# SCH4_RGB_Indicator.net
KiCad netlist of a schematic drawn in Altium Designer
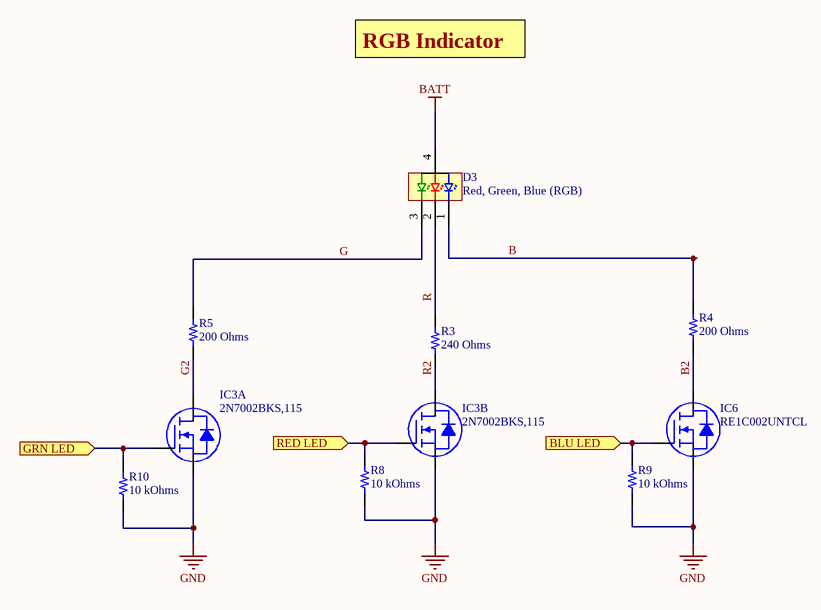
[diagram p0: SCH4_RGB_Indicator.SchDoc]

(export (version "E")
  (design (tool "Eeschema 10.0.6"))
  (components
    (comp (ref "D3")
      (value "Red, Green, Blue (RGB)")
      (footprint "Citizen CL-505S-X-SD-T")
      (description "LED TRI TOP FIRING 1.0 X 1.0")
      (fields (field (name "PART NUMBER") "CL-505S-X-SD-T") (field (name "MANUFACTURER") "Citizen"))
      (libsource (lib "Celestial Altium Library - altium_library") (part "RGB LED Citizen CL-505"))
    )
    (comp (ref "IC3")
      (value "2N7002BKS,115")
      (footprint "NXP SOT-363")
      (description "MOSFET 2N-CH 60V 0.3A 6TSSOP")
      (fields (field (name "MANUFACTURER") "Nexperia USA Inc."))
      (libsource (lib "Celestial Altium Library - altium_library") (part "NEXPERIA DUAL MOSFET N-CH SOT363"))
    )
    (comp (ref "IC6")
      (value "RE1C002UNTCL")
      (footprint "ROHM SC-89-SOT-490")
      (description "MOSFET N-CH 20V 0.2A EMT3")
      (fields (field (name "MANUFACTURER") "Rohm Semiconductor"))
      (libsource (lib "Celestial Altium Library - altium_library") (part "ROHM MOSFET N-CH SC-89"))
    )
    (comp (ref "R3")
      (value "240 Ohms")
      (footprint "RES 0402_1005")
      (description "RES SMD 240 OHM 0.5% 1/16W 0402")
      (fields (field (name "PART NUMBER") "RR0510P-241-D") (field (name "MANUFACTURER") "Susumu"))
      (libsource (lib "Celestial Altium Library - altium_library") (part "Resistor"))
    )
    (comp (ref "R4")
      (value "200 Ohms")
      (footprint "RES 0402_1005")
      (description "RES SMD 200 OHM 0.5% 1/16W 0402")
      (fields (field (name "PART NUMBER") "RR0510P-201-D") (field (name "MANUFACTURER") "Susumu"))
      (libsource (lib "Celestial Altium Library - altium_library") (part "Resistor"))
    )
    (comp (ref "R5")
      (value "200 Ohms")
      (footprint "RES 0402_1005")
      (description "RES SMD 200 OHM 0.5% 1/16W 0402")
      (fields (field (name "PART NUMBER") "RR0510P-201-D") (field (name "MANUFACTURER") "Susumu"))
      (libsource (lib "Celestial Altium Library - altium_library") (part "Resistor"))
    )
    (comp (ref "R8")
      (value "10 kOhms")
      (footprint "RES 0402_1005")
      (description "RES 10 KOHM 1% 1/16W 0402")
      (fields (field (name "PART NUMBER") "ASC0402-10KF1") (field (name "MANUFACTURER") "Riedon"))
      (libsource (lib "Celestial Altium Library - altium_library") (part "Resistor"))
    )
    (comp (ref "R9")
      (value "10 kOhms")
      (footprint "RES 0402_1005")
      (description "RES 10 KOHM 1% 1/16W 0402")
      (fields (field (name "PART NUMBER") "ASC0402-10KF1") (field (name "MANUFACTURER") "Riedon"))
      (libsource (lib "Celestial Altium Library - altium_library") (part "Resistor"))
    )
    (comp (ref "R10")
      (value "10 kOhms")
      (footprint "RES 0402_1005")
      (description "RES 10 KOHM 1% 1/16W 0402")
      (fields (field (name "PART NUMBER") "ASC0402-10KF1") (field (name "MANUFACTURER") "Riedon"))
      (libsource (lib "Celestial Altium Library - altium_library") (part "Resistor"))
    )
  )
  (nets
    (net (code "2") (name "/B") (class "Default")
      (node (ref "D3") (pin "1") (pinfunction "C1_1") (pintype "passive"))
      (node (ref "R4") (pin "2") (pinfunction "2_2") (pintype "passive"))
    )
    (net (code "3") (name "/B2") (class "Default")
      (node (ref "IC6") (pin "3") (pinfunction "D_3") (pintype "passive"))
      (node (ref "R4") (pin "1") (pinfunction "1_1") (pintype "passive"))
    )
    (net (code "4") (name "/BLU LED") (class "Default")
      (node (ref "IC6") (pin "1") (pinfunction "G_1") (pintype "passive"))
      (node (ref "R9") (pin "2") (pinfunction "2_2") (pintype "passive"))
    )
    (net (code "5") (name "/G") (class "Default")
      (node (ref "D3") (pin "3") (pinfunction "C3_3") (pintype "passive"))
      (node (ref "R5") (pin "2") (pinfunction "2_2") (pintype "passive"))
    )
    (net (code "6") (name "/G2") (class "Default")
      (node (ref "IC3") (pin "6") (pinfunction "D1_6") (pintype "passive"))
      (node (ref "R5") (pin "1") (pinfunction "1_1") (pintype "passive"))
    )
    (net (code "7") (name "/GRN LED") (class "Default")
      (node (ref "IC3") (pin "2") (pinfunction "G1_2") (pintype "passive"))
      (node (ref "R10") (pin "2") (pinfunction "2_2") (pintype "passive"))
    )
    (net (code "8") (name "/R") (class "Default")
      (node (ref "D3") (pin "2") (pinfunction "C2_2") (pintype "passive"))
      (node (ref "R3") (pin "2") (pinfunction "2_2") (pintype "passive"))
    )
    (net (code "9") (name "/R2") (class "Default")
      (node (ref "IC3") (pin "3") (pinfunction "D2_3") (pintype "passive"))
      (node (ref "R3") (pin "1") (pinfunction "1_1") (pintype "passive"))
    )
    (net (code "10") (name "/RED LED") (class "Default")
      (node (ref "IC3") (pin "5") (pinfunction "G2_5") (pintype "passive"))
      (node (ref "R8") (pin "2") (pinfunction "2_2") (pintype "passive"))
    )
    (net (code "11") (name "BATT") (class "Default")
      (node (ref "D3") (pin "4") (pinfunction "A3_4") (pintype "passive"))
    )
    (net (code "12") (name "GND") (class "Default")
      (node (ref "IC3") (pin "1") (pinfunction "S1_1") (pintype "passive"))
      (node (ref "IC3") (pin "4") (pinfunction "S2_4") (pintype "passive"))
      (node (ref "IC6") (pin "2") (pinfunction "S_2") (pintype "passive"))
      (node (ref "R10") (pin "1") (pinfunction "1_1") (pintype "passive"))
      (node (ref "R8") (pin "1") (pinfunction "1_1") (pintype "passive"))
      (node (ref "R9") (pin "1") (pinfunction "1_1") (pintype "passive"))
    )
  )
)
